# IMU_Connectors.net
KiCad netlist of a schematic drawn in Altium Designer
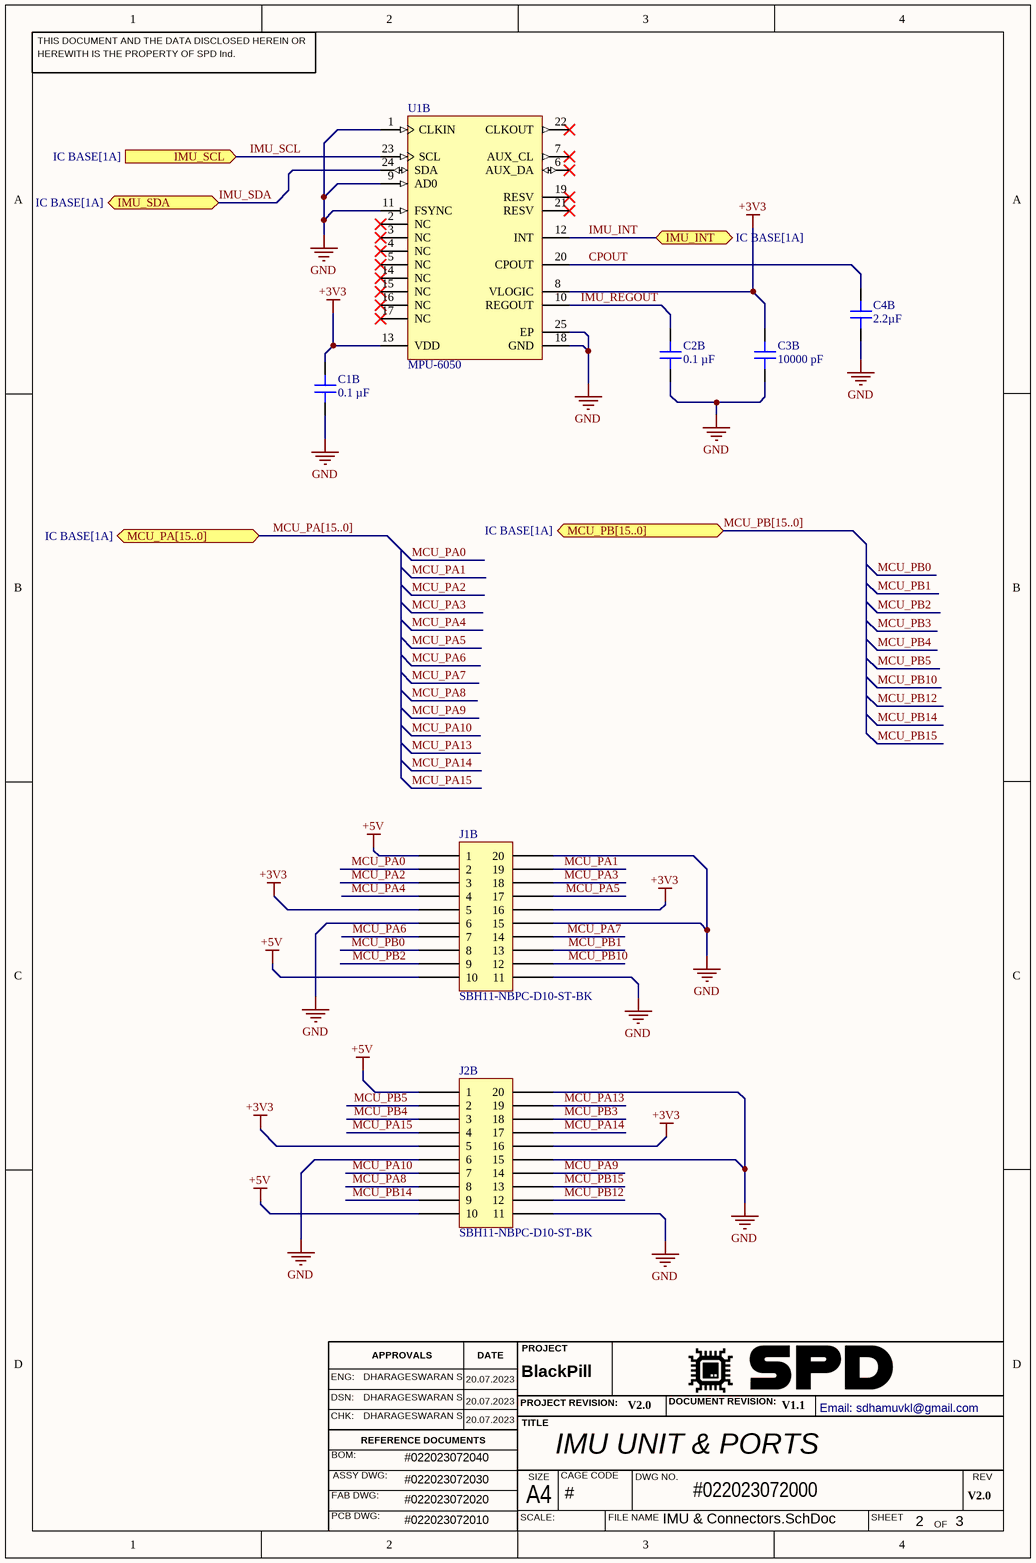
[diagram p0: IMU & Connectors.SchDoc]

(export (version "E")
  (design (tool "Eeschema 10.0.6"))
  (components
    (comp (ref "C1B")
      (value "0.1 µF")
      (footprint "CAP 0402_1005")
      (description "CAP CER 100NF 10V X7R 0402")
      (fields
        (field (name "PART NUMBER") "CL05B104KP5VPNC")
        (field (name "MANUFACTURER") "Samsung Electro-Mechanics")
      )
      (libsource (lib "Postgres Altium Library - altium_library") (part "Capacitor"))
    )
    (comp (ref "C2B")
      (value "0.1 µF")
      (footprint "CAP 0402_1005")
      (description "CAP CER 100NF 10V X7R 0402")
      (fields
        (field (name "PART NUMBER") "CL05B104KP5VPNC")
        (field (name "MANUFACTURER") "Samsung Electro-Mechanics")
      )
      (libsource (lib "Postgres Altium Library - altium_library") (part "Capacitor"))
    )
    (comp (ref "C3B")
      (value "10000 pF")
      (footprint "CAP 0402_1005")
      (description "CAP CER 0402 10NF 16V X7R 10%")
      (fields (field (name "PART NUMBER") "C0402C103K4REC7411") (field (name "MANUFACTURER") "KEMET"))
      (libsource (lib "Postgres Altium Library - altium_library") (part "Capacitor"))
    )
    (comp (ref "C4B")
      (value "2.2µF")
      (footprint "CAP 0402_1005")
      (description "CAP CER 2.2UF 10V X5R 0402")
      (fields (field (name "PART NUMBER") "0402ZD225KAT2A") (field (name "MANUFACTURER") "AVX Corporation"))
      (libsource (lib "Postgres Altium Library - altium_library") (part "Capacitor"))
    )
    (comp (ref "J1B")
      (value "SBH11-NBPC-D10-ST-BK")
      (footprint "SULLINS SBH11-NBPC-D10-ST-BK")
      (description "CONN HEADER VERT 20POS 2.54MM")
      (fields (field (name "MANUFACTURER") "Sullins Connector Solutions"))
      (libsource (lib "Postgres Altium Library - altium_library") (part "20 Pin Dual Row"))
    )
    (comp (ref "J2B")
      (value "SBH11-NBPC-D10-ST-BK")
      (footprint "SULLINS SBH11-NBPC-D10-ST-BK")
      (description "CONN HEADER VERT 20POS 2.54MM")
      (fields (field (name "MANUFACTURER") "Sullins Connector Solutions"))
      (libsource (lib "Postgres Altium Library - altium_library") (part "20 Pin Dual Row"))
    )
    (comp (ref "U1B")
      (value "MPU-6050")
      (footprint "QFN50P400X400X95-24N")
      (description "MPU-6050 series Accelerometer, Gyroscope, 3 Axis Sensor Evaluation Board")
      (fields (field (name "MF") "TDK InvenSense"))
      (libsource (lib "MPU-6050") (part "MPU-6050"))
    )
  )
  (nets
    (net (code "9") (name "+3V3") (class "Default")
      (node (ref "C1B") (pin "2") (pinfunction "2_2") (pintype "passive"))
      (node (ref "C3B") (pin "2") (pinfunction "2_2") (pintype "passive"))
      (node (ref "J1B") (pin "16") (pinfunction "16_16") (pintype "passive"))
      (node (ref "J1B") (pin "5") (pinfunction "5_5") (pintype "passive"))
      (node (ref "J2B") (pin "16") (pinfunction "16_16") (pintype "passive"))
      (node (ref "J2B") (pin "5") (pinfunction "5_5") (pintype "passive"))
      (node (ref "U1B") (pin "13") (pinfunction "VDD_13") (pintype "power_in"))
      (node (ref "U1B") (pin "8") (pinfunction "VLOGIC_8") (pintype "power_in"))
    )
    (net (code "10") (name "+5V") (class "Default")
      (node (ref "J1B") (pin "1") (pinfunction "1_1") (pintype "passive"))
      (node (ref "J1B") (pin "10") (pinfunction "10_10") (pintype "passive"))
      (node (ref "J2B") (pin "1") (pinfunction "1_1") (pintype "passive"))
      (node (ref "J2B") (pin "10") (pinfunction "10_10") (pintype "passive"))
    )
    (net (code "11") (name "/CPOUT") (class "Default")
      (node (ref "C4B") (pin "2") (pinfunction "2_2") (pintype "passive"))
      (node (ref "U1B") (pin "20") (pinfunction "CPOUT_20") (pintype "passive"))
    )
    (net (code "12") (name "/IMU_INT") (class "Default")
      (node (ref "U1B") (pin "12") (pinfunction "INT_12") (pintype "open_collector"))
    )
    (net (code "13") (name "/IMU_REGOUT") (class "Default")
      (node (ref "C2B") (pin "2") (pinfunction "2_2") (pintype "passive"))
      (node (ref "U1B") (pin "10") (pinfunction "REGOUT_10") (pintype "passive"))
    )
    (net (code "14") (name "/IMU_SCL") (class "Default")
      (node (ref "U1B") (pin "23") (pinfunction "SCL_23") (pintype "input"))
    )
    (net (code "15") (name "/IMU_SDA") (class "Default")
      (node (ref "U1B") (pin "24") (pinfunction "SDA_24") (pintype "bidirectional"))
    )
    (net (code "16") (name "/MCU_PA0") (class "Default")
      (node (ref "J1B") (pin "2") (pinfunction "2_2") (pintype "passive"))
    )
    (net (code "17") (name "/MCU_PA1") (class "Default")
      (node (ref "J1B") (pin "19") (pinfunction "19_19") (pintype "passive"))
    )
    (net (code "18") (name "/MCU_PA2") (class "Default")
      (node (ref "J1B") (pin "3") (pinfunction "3_3") (pintype "passive"))
    )
    (net (code "19") (name "/MCU_PA3") (class "Default")
      (node (ref "J1B") (pin "18") (pinfunction "18_18") (pintype "passive"))
    )
    (net (code "20") (name "/MCU_PA4") (class "Default")
      (node (ref "J1B") (pin "4") (pinfunction "4_4") (pintype "passive"))
    )
    (net (code "21") (name "/MCU_PA5") (class "Default")
      (node (ref "J1B") (pin "17") (pinfunction "17_17") (pintype "passive"))
    )
    (net (code "22") (name "/MCU_PA6") (class "Default")
      (node (ref "J1B") (pin "7") (pinfunction "7_7") (pintype "passive"))
    )
    (net (code "23") (name "/MCU_PA7") (class "Default")
      (node (ref "J1B") (pin "14") (pinfunction "14_14") (pintype "passive"))
    )
    (net (code "24") (name "/MCU_PA8") (class "Default")
      (node (ref "J2B") (pin "8") (pinfunction "8_8") (pintype "passive"))
    )
    (net (code "25") (name "/MCU_PA9") (class "Default")
      (node (ref "J2B") (pin "14") (pinfunction "14_14") (pintype "passive"))
    )
    (net (code "26") (name "/MCU_PA10") (class "Default")
      (node (ref "J2B") (pin "7") (pinfunction "7_7") (pintype "passive"))
    )
    (net (code "27") (name "/MCU_PA13") (class "Default")
      (node (ref "J2B") (pin "19") (pinfunction "19_19") (pintype "passive"))
    )
    (net (code "28") (name "/MCU_PA14") (class "Default")
      (node (ref "J2B") (pin "17") (pinfunction "17_17") (pintype "passive"))
    )
    (net (code "29") (name "/MCU_PA15") (class "Default")
      (node (ref "J2B") (pin "4") (pinfunction "4_4") (pintype "passive"))
    )
    (net (code "31") (name "/MCU_PB0") (class "Default")
      (node (ref "J1B") (pin "8") (pinfunction "8_8") (pintype "passive"))
    )
    (net (code "32") (name "/MCU_PB1") (class "Default")
      (node (ref "J1B") (pin "13") (pinfunction "13_13") (pintype "passive"))
    )
    (net (code "33") (name "/MCU_PB2") (class "Default")
      (node (ref "J1B") (pin "9") (pinfunction "9_9") (pintype "passive"))
    )
    (net (code "34") (name "/MCU_PB3") (class "Default")
      (node (ref "J2B") (pin "18") (pinfunction "18_18") (pintype "passive"))
    )
    (net (code "35") (name "/MCU_PB4") (class "Default")
      (node (ref "J2B") (pin "3") (pinfunction "3_3") (pintype "passive"))
    )
    (net (code "36") (name "/MCU_PB5") (class "Default")
      (node (ref "J2B") (pin "2") (pinfunction "2_2") (pintype "passive"))
    )
    (net (code "37") (name "/MCU_PB10") (class "Default")
      (node (ref "J1B") (pin "12") (pinfunction "12_12") (pintype "passive"))
    )
    (net (code "38") (name "/MCU_PB12") (class "Default")
      (node (ref "J2B") (pin "12") (pinfunction "12_12") (pintype "passive"))
    )
    (net (code "39") (name "/MCU_PB14") (class "Default")
      (node (ref "J2B") (pin "9") (pinfunction "9_9") (pintype "passive"))
    )
    (net (code "40") (name "/MCU_PB15") (class "Default")
      (node (ref "J2B") (pin "13") (pinfunction "13_13") (pintype "passive"))
    )
    (net (code "42") (name "GND") (class "Default")
      (node (ref "C1B") (pin "1") (pinfunction "1_1") (pintype "passive"))
      (node (ref "C2B") (pin "1") (pinfunction "1_1") (pintype "passive"))
      (node (ref "C3B") (pin "1") (pinfunction "1_1") (pintype "passive"))
      (node (ref "C4B") (pin "1") (pinfunction "1_1") (pintype "passive"))
      (node (ref "J1B") (pin "11") (pinfunction "11_11") (pintype "passive"))
      (node (ref "J1B") (pin "15") (pinfunction "15_15") (pintype "passive"))
      (node (ref "J1B") (pin "20") (pinfunction "20_20") (pintype "passive"))
      (node (ref "J1B") (pin "6") (pinfunction "6_6") (pintype "passive"))
      (node (ref "J2B") (pin "11") (pinfunction "11_11") (pintype "passive"))
      (node (ref "J2B") (pin "15") (pinfunction "15_15") (pintype "passive"))
      (node (ref "J2B") (pin "20") (pinfunction "20_20") (pintype "passive"))
      (node (ref "J2B") (pin "6") (pinfunction "6_6") (pintype "passive"))
      (node (ref "U1B") (pin "1") (pinfunction "CLKIN_1") (pintype "input"))
      (node (ref "U1B") (pin "11") (pinfunction "FSYNC_11") (pintype "input"))
      (node (ref "U1B") (pin "18") (pinfunction "GND_18") (pintype "power_in"))
      (node (ref "U1B") (pin "25") (pinfunction "EP_25") (pintype "power_in"))
      (node (ref "U1B") (pin "9") (pinfunction "AD0_9") (pintype "input"))
    )
    (net (code "43") (name "unconnected-(U1B-AUX_CL-Pad7)") (class "Default")
      (node (ref "U1B") (pin "7") (pinfunction "AUX_CL_7") (pintype "output+no_connect"))
    )
    (net (code "44") (name "unconnected-(U1B-AUX_DA-Pad6)") (class "Default")
      (node (ref "U1B") (pin "6") (pinfunction "AUX_DA_6") (pintype "bidirectional+no_connect"))
    )
    (net (code "45") (name "unconnected-(U1B-CLKOUT-Pad22)") (class "Default")
      (node (ref "U1B") (pin "22") (pinfunction "CLKOUT_22") (pintype "output+no_connect"))
    )
    (net (code "46") (name "unconnected-(U1B-NC-Pad2)") (class "Default")
      (node (ref "U1B") (pin "2") (pinfunction "NC_2") (pintype "passive+no_connect"))
    )
    (net (code "47") (name "unconnected-(U1B-NC-Pad3)") (class "Default")
      (node (ref "U1B") (pin "3") (pinfunction "NC_3") (pintype "passive+no_connect"))
    )
    (net (code "48") (name "unconnected-(U1B-NC-Pad4)") (class "Default")
      (node (ref "U1B") (pin "4") (pinfunction "NC_4") (pintype "passive+no_connect"))
    )
    (net (code "49") (name "unconnected-(U1B-NC-Pad5)") (class "Default")
      (node (ref "U1B") (pin "5") (pinfunction "NC_5") (pintype "passive+no_connect"))
    )
    (net (code "50") (name "unconnected-(U1B-NC-Pad14)") (class "Default")
      (node (ref "U1B") (pin "14") (pinfunction "NC_14") (pintype "passive+no_connect"))
    )
    (net (code "51") (name "unconnected-(U1B-NC-Pad15)") (class "Default")
      (node (ref "U1B") (pin "15") (pinfunction "NC_15") (pintype "passive+no_connect"))
    )
    (net (code "52") (name "unconnected-(U1B-NC-Pad16)") (class "Default")
      (node (ref "U1B") (pin "16") (pinfunction "NC_16") (pintype "passive+no_connect"))
    )
    (net (code "53") (name "unconnected-(U1B-NC-Pad17)") (class "Default")
      (node (ref "U1B") (pin "17") (pinfunction "NC_17") (pintype "passive+no_connect"))
    )
    (net (code "54") (name "unconnected-(U1B-RESV-Pad19)") (class "Default")
      (node (ref "U1B") (pin "19") (pinfunction "RESV_19") (pintype "passive+no_connect"))
    )
    (net (code "55") (name "unconnected-(U1B-RESV-Pad21)") (class "Default")
      (node (ref "U1B") (pin "21") (pinfunction "RESV_21") (pintype "passive+no_connect"))
    )
  )
)
